# debug_board.net
KiCad netlist of a schematic drawn in EAGLE
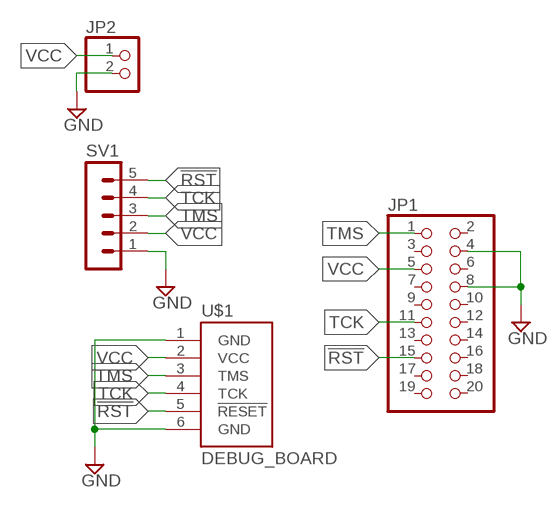
[diagram p0: schematic, sheet 1]

(export (version "E")
  (design (tool "Eeschema 10.0.6"))
  (components
    (comp (ref "JP1")
      (value "PINHD-2X10")
      (footprint "eagle-import:2X10")
      (libsource (lib "eagle-import") (part "PINHD-2X10"))
    )
    (comp (ref "JP2")
      (value "PINHD-1X2")
      (footprint "eagle-import:1X02")
      (libsource (lib "eagle-import") (part "PINHD-1X2"))
    )
    (comp (ref "SV1")
      (value "MA05-1")
      (footprint "eagle-import:MA05-1")
      (libsource (lib "eagle-import") (part "MA05-1"))
    )
    (comp (ref "U$1")
      (value "DEBUG_BOARD")
      (footprint "eagle-import:DEBUG_BOARD")
      (libsource (lib "eagle-import") (part "DEBUG_BOARD"))
    )
  )
  (nets
    (net (code "1") (name "/~{RST}") (class "Default")
      (node (ref "JP1") (pin "15") (pinfunction "15_15") (pintype "passive"))
      (node (ref "SV1") (pin "5") (pinfunction "5_5") (pintype "passive"))
      (node (ref "U$1") (pin "5") (pinfunction "~{RESET}_5") (pintype "bidirectional"))
    )
    (net (code "2") (name "GND") (class "Default")
      (node (ref "JP1") (pin "4") (pinfunction "4_4") (pintype "passive"))
      (node (ref "JP1") (pin "8") (pinfunction "8_8") (pintype "passive"))
      (node (ref "JP2") (pin "2") (pinfunction "2_2") (pintype "passive"))
      (node (ref "SV1") (pin "1") (pinfunction "1_1") (pintype "passive"))
      (node (ref "U$1") (pin "1") (pinfunction "GND_1") (pintype "bidirectional"))
      (node (ref "U$1") (pin "6") (pinfunction "GND_6") (pintype "bidirectional"))
    )
    (net (code "3") (name "TCK") (class "Default")
      (node (ref "JP1") (pin "11") (pinfunction "11_11") (pintype "passive"))
      (node (ref "SV1") (pin "4") (pinfunction "4_4") (pintype "passive"))
      (node (ref "U$1") (pin "4") (pinfunction "TCK_4") (pintype "bidirectional"))
    )
    (net (code "4") (name "TMS") (class "Default")
      (node (ref "JP1") (pin "1") (pinfunction "1_1") (pintype "passive"))
      (node (ref "SV1") (pin "3") (pinfunction "3_3") (pintype "passive"))
      (node (ref "U$1") (pin "3") (pinfunction "TMS_3") (pintype "bidirectional"))
    )
    (net (code "5") (name "VCC") (class "Default")
      (node (ref "JP1") (pin "5") (pinfunction "5_5") (pintype "passive"))
      (node (ref "JP2") (pin "1") (pinfunction "1_1") (pintype "passive"))
      (node (ref "SV1") (pin "2") (pinfunction "2_2") (pintype "passive"))
      (node (ref "U$1") (pin "2") (pinfunction "VCC_2") (pintype "bidirectional"))
    )
    (net (code "6") (name "unconnected-(JP1-Pad2)") (class "Default")
      (node (ref "JP1") (pin "2") (pinfunction "2_2") (pintype "passive"))
    )
    (net (code "7") (name "unconnected-(JP1-Pad3)") (class "Default")
      (node (ref "JP1") (pin "3") (pinfunction "3_3") (pintype "passive"))
    )
    (net (code "8") (name "unconnected-(JP1-Pad6)") (class "Default")
      (node (ref "JP1") (pin "6") (pinfunction "6_6") (pintype "passive"))
    )
    (net (code "9") (name "unconnected-(JP1-Pad7)") (class "Default")
      (node (ref "JP1") (pin "7") (pinfunction "7_7") (pintype "passive"))
    )
    (net (code "10") (name "unconnected-(JP1-Pad9)") (class "Default")
      (node (ref "JP1") (pin "9") (pinfunction "9_9") (pintype "passive"))
    )
    (net (code "11") (name "unconnected-(JP1-Pad10)") (class "Default")
      (node (ref "JP1") (pin "10") (pinfunction "10_10") (pintype "passive"))
    )
    (net (code "12") (name "unconnected-(JP1-Pad12)") (class "Default")
      (node (ref "JP1") (pin "12") (pinfunction "12_12") (pintype "passive"))
    )
    (net (code "13") (name "unconnected-(JP1-Pad13)") (class "Default")
      (node (ref "JP1") (pin "13") (pinfunction "13_13") (pintype "passive"))
    )
    (net (code "14") (name "unconnected-(JP1-Pad14)") (class "Default")
      (node (ref "JP1") (pin "14") (pinfunction "14_14") (pintype "passive"))
    )
    (net (code "15") (name "unconnected-(JP1-Pad16)") (class "Default")
      (node (ref "JP1") (pin "16") (pinfunction "16_16") (pintype "passive"))
    )
    (net (code "16") (name "unconnected-(JP1-Pad17)") (class "Default")
      (node (ref "JP1") (pin "17") (pinfunction "17_17") (pintype "passive"))
    )
    (net (code "17") (name "unconnected-(JP1-Pad18)") (class "Default")
      (node (ref "JP1") (pin "18") (pinfunction "18_18") (pintype "passive"))
    )
    (net (code "18") (name "unconnected-(JP1-Pad19)") (class "Default")
      (node (ref "JP1") (pin "19") (pinfunction "19_19") (pintype "passive"))
    )
    (net (code "19") (name "unconnected-(JP1-Pad20)") (class "Default")
      (node (ref "JP1") (pin "20") (pinfunction "20_20") (pintype "passive"))
    )
  )
)
